# USB_MINER_CH340_c.net
KiCad netlist of a schematic drawn in EAGLE
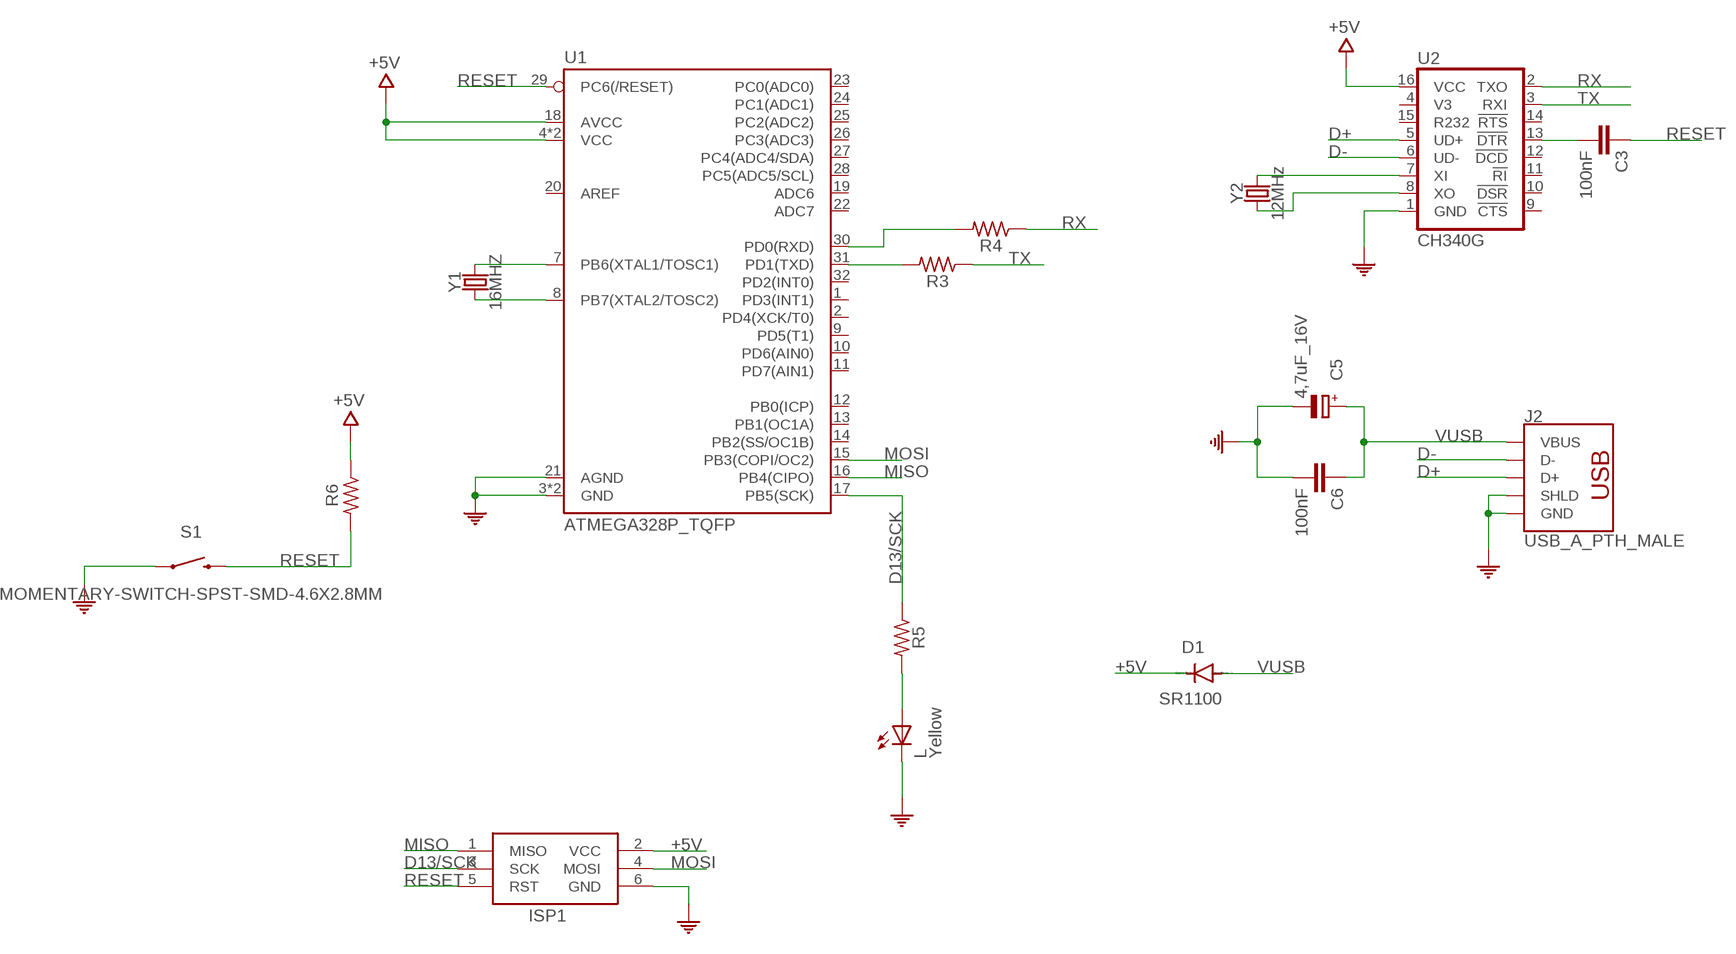
[diagram p0: schematic, sheet 1]

(export (version "E")
  (design (tool "Eeschema 10.0.6"))
  (components
    (comp (ref "C3")
      (value "100nF")
      (footprint "eagle-import:C0805K")
      (libsource (lib "eagle-import") (part "C-EUC0805K"))
    )
    (comp (ref "C5")
      (value "4,7uF_16V")
      (footprint "eagle-import:TAN-A")
      (fields (field (name "PART_NUMBER") "TAJA475MO16RNJ"))
      (libsource (lib "eagle-import") (part "0833_TAJA475MO16RNJ"))
    )
    (comp (ref "C6")
      (value "100nF")
      (footprint "eagle-import:C0805K")
      (libsource (lib "eagle-import") (part "C-EUC0805K"))
    )
    (comp (ref "D1")
      (value "SR1100")
      (footprint "eagle-import:DO-214AC")
      (libsource (lib "eagle-import") (part "DIODE-DO-214AC"))
    )
    (comp (ref "ISP1")
      (value "AVRISP-6")
      (footprint "eagle-import:AVRISP")
      (libsource (lib "eagle-import") (part "AVRISP-6"))
    )
    (comp (ref "J2")
      (value "USB_A_PTH_MALE")
      (footprint "eagle-import:USB-A-H")
      (libsource (lib "eagle-import") (part "USB_A_PTH_MALE"))
    )
    (comp (ref "L")
      (value "Yellow")
      (footprint "eagle-import:CHIPLED_0805")
      (fields (field (name "PART_NUMBER") "KPT-2012YC"))
      (libsource (lib "eagle-import") (part "0044_KPT-2012YC"))
    )
    (comp (ref "R3")
      (value "1k")
      (footprint "eagle-import:R0805")
      (libsource (lib "eagle-import") (part "R-US_R0805"))
    )
    (comp (ref "R4")
      (value "1k")
      (footprint "eagle-import:R0805")
      (libsource (lib "eagle-import") (part "R-US_R0805"))
    )
    (comp (ref "R5")
      (value "1k")
      (footprint "eagle-import:R0805")
      (libsource (lib "eagle-import") (part "R-US_R0805"))
    )
    (comp (ref "R6")
      (value "1k")
      (footprint "eagle-import:R0805")
      (libsource (lib "eagle-import") (part "R-US_R0805"))
    )
    (comp (ref "S1")
      (value "MOMENTARY-SWITCH-SPST-SMD-4.6X2.8MM")
      (footprint "eagle-import:TACTILE_SWITCH_SMD_4.6X2.8MM")
      (libsource (lib "eagle-import") (part "MOMENTARY-SWITCH-SPST-SMD-4.6X2.8MM"))
    )
    (comp (ref "U1")
      (value "ATMEGA328P_TQFP")
      (footprint "eagle-import:TQFP32-08")
      (libsource (lib "eagle-import") (part "ATMEGA328P_TQFP"))
    )
    (comp (ref "U2")
      (value "CH340G")
      (footprint "eagle-import:SO016")
      (libsource (lib "eagle-import") (part "CH340GSMD"))
    )
    (comp (ref "Y1")
      (value "16MHZ")
      (footprint "eagle-import:HC49UP")
      (libsource (lib "eagle-import") (part "CRYSTALSMD-HC49UP"))
    )
    (comp (ref "Y2")
      (value "12MHz")
      (footprint "eagle-import:HC49UP")
      (libsource (lib "eagle-import") (part "CRYSTALSMD-HC49UP"))
    )
  )
  (nets
    (net (code "1") (name "+5V") (class "Default")
      (node (ref "D1") (pin "C") (pinfunction "C_C") (pintype "passive"))
      (node (ref "ISP1") (pin "2") (pinfunction "VCC_2") (pintype "power_in"))
      (node (ref "R6") (pin "1") (pinfunction "1_1") (pintype "passive"))
      (node (ref "U1") (pin "18") (pinfunction "AVCC_18") (pintype "bidirectional"))
      (node (ref "U1") (pin "4") (pinfunction "VCC_4") (pintype "bidirectional"))
      (node (ref "U1") (pin "6") (pinfunction "VCC_6") (pintype "bidirectional"))
      (node (ref "U2") (pin "16") (pinfunction "VCC_16") (pintype "bidirectional"))
    )
    (net (code "2") (name "/D+") (class "Default")
      (node (ref "J2") (pin "D+") (pinfunction "D+_D+") (pintype "bidirectional"))
      (node (ref "U2") (pin "5") (pinfunction "UD+_5") (pintype "bidirectional"))
    )
    (net (code "3") (name "/D-") (class "Default")
      (node (ref "J2") (pin "D-") (pinfunction "D-_D-") (pintype "bidirectional"))
      (node (ref "U2") (pin "6") (pinfunction "UD-_6") (pintype "bidirectional"))
    )
    (net (code "4") (name "/D13{slash}SCK") (class "Default")
      (node (ref "ISP1") (pin "3") (pinfunction "SCK_3") (pintype "output"))
      (node (ref "R5") (pin "1") (pinfunction "1_1") (pintype "passive"))
      (node (ref "U1") (pin "17") (pinfunction "PB5(SCK)_17") (pintype "bidirectional"))
    )
    (net (code "5") (name "/MISO") (class "Default")
      (node (ref "ISP1") (pin "1") (pinfunction "MISO_1") (pintype "input"))
      (node (ref "U1") (pin "16") (pinfunction "PB4(CIPO)_16") (pintype "bidirectional"))
    )
    (net (code "6") (name "/MOSI") (class "Default")
      (node (ref "ISP1") (pin "4") (pinfunction "MOSI_4") (pintype "output"))
      (node (ref "U1") (pin "15") (pinfunction "PB3(COPI/OC2)_15") (pintype "bidirectional"))
    )
    (net (code "7") (name "/RESET") (class "Default")
      (node (ref "C3") (pin "1") (pinfunction "1_1") (pintype "passive"))
      (node (ref "ISP1") (pin "5") (pinfunction "RST_5") (pintype "output"))
      (node (ref "R6") (pin "2") (pinfunction "2_2") (pintype "passive"))
      (node (ref "S1") (pin "3") (pinfunction "2_3") (pintype "passive"))
      (node (ref "S1") (pin "4") (pinfunction "2_4") (pintype "passive"))
      (node (ref "U1") (pin "29") (pinfunction "PC6(/RESET)_29") (pintype "bidirectional"))
    )
    (net (code "8") (name "/RX") (class "Default")
      (node (ref "R4") (pin "1") (pinfunction "1_1") (pintype "passive"))
      (node (ref "U2") (pin "2") (pinfunction "TXO_2") (pintype "bidirectional"))
    )
    (net (code "9") (name "/TX") (class "Default")
      (node (ref "R3") (pin "1") (pinfunction "1_1") (pintype "passive"))
      (node (ref "U2") (pin "3") (pinfunction "RXI_3") (pintype "bidirectional"))
    )
    (net (code "10") (name "/VUSB") (class "Default")
      (node (ref "C5") (pin "1") (pinfunction "+_1") (pintype "passive"))
      (node (ref "C6") (pin "1") (pinfunction "1_1") (pintype "passive"))
      (node (ref "D1") (pin "A") (pinfunction "A_A") (pintype "passive"))
      (node (ref "J2") (pin "VBUS") (pinfunction "VBUS_VBUS") (pintype "power_in"))
    )
    (net (code "11") (name "COM") (class "Default")
      (node (ref "C5") (pin "2") (pinfunction "-_2") (pintype "passive"))
      (node (ref "C6") (pin "2") (pinfunction "2_2") (pintype "passive"))
      (node (ref "ISP1") (pin "6") (pinfunction "GND_6") (pintype "power_in"))
      (node (ref "J2") (pin "GND") (pinfunction "GND_GND") (pintype "power_in"))
      (node (ref "J2") (pin "SHLD1") (pinfunction "SHLD_SHLD1") (pintype "bidirectional"))
      (node (ref "J2") (pin "SHLD2") (pinfunction "SHLD_SHLD2") (pintype "bidirectional"))
      (node (ref "L") (pin "C") (pinfunction "C_C") (pintype "passive"))
      (node (ref "S1") (pin "1") (pinfunction "1_1") (pintype "passive"))
      (node (ref "S1") (pin "2") (pinfunction "1_2") (pintype "passive"))
      (node (ref "U1") (pin "21") (pinfunction "AGND_21") (pintype "bidirectional"))
      (node (ref "U1") (pin "3") (pinfunction "GND_3") (pintype "bidirectional"))
      (node (ref "U1") (pin "5") (pinfunction "GND_5") (pintype "bidirectional"))
      (node (ref "U2") (pin "1") (pinfunction "GND_1") (pintype "bidirectional"))
    )
    (net (code "12") (name "Net-(L-PadA)") (class "Default")
      (node (ref "L") (pin "A") (pinfunction "A_A") (pintype "passive"))
      (node (ref "R5") (pin "2") (pinfunction "2_2") (pintype "passive"))
    )
    (net (code "13") (name "Net-(U1-PB6(XTAL1{slash}TOSC1))") (class "Default")
      (node (ref "U1") (pin "7") (pinfunction "PB6(XTAL1/TOSC1)_7") (pintype "bidirectional"))
      (node (ref "Y1") (pin "2") (pinfunction "2_2") (pintype "passive"))
    )
    (net (code "14") (name "Net-(U1-PB7(XTAL2{slash}TOSC2))") (class "Default")
      (node (ref "U1") (pin "8") (pinfunction "PB7(XTAL2/TOSC2)_8") (pintype "bidirectional"))
      (node (ref "Y1") (pin "1") (pinfunction "1_1") (pintype "passive"))
    )
    (net (code "15") (name "Net-(U1-PD0(RXD))") (class "Default")
      (node (ref "R4") (pin "2") (pinfunction "2_2") (pintype "passive"))
      (node (ref "U1") (pin "30") (pinfunction "PD0(RXD)_30") (pintype "bidirectional"))
    )
    (net (code "16") (name "Net-(U1-PD1(TXD))") (class "Default")
      (node (ref "R3") (pin "2") (pinfunction "2_2") (pintype "passive"))
      (node (ref "U1") (pin "31") (pinfunction "PD1(TXD)_31") (pintype "bidirectional"))
    )
    (net (code "17") (name "Net-(U2-XI)") (class "Default")
      (node (ref "U2") (pin "7") (pinfunction "XI_7") (pintype "bidirectional"))
      (node (ref "Y2") (pin "2") (pinfunction "2_2") (pintype "passive"))
    )
    (net (code "18") (name "Net-(U2-XO)") (class "Default")
      (node (ref "U2") (pin "8") (pinfunction "XO_8") (pintype "bidirectional"))
      (node (ref "Y2") (pin "1") (pinfunction "1_1") (pintype "passive"))
    )
    (net (code "19") (name "Net-(U2-~{DTR})") (class "Default")
      (node (ref "C3") (pin "2") (pinfunction "2_2") (pintype "passive"))
      (node (ref "U2") (pin "13") (pinfunction "~{DTR}_13") (pintype "bidirectional"))
    )
    (net (code "20") (name "unconnected-(U1-ADC6-Pad19)") (class "Default")
      (node (ref "U1") (pin "19") (pinfunction "ADC6_19") (pintype "bidirectional"))
    )
    (net (code "21") (name "unconnected-(U1-ADC7-Pad22)") (class "Default")
      (node (ref "U1") (pin "22") (pinfunction "ADC7_22") (pintype "bidirectional"))
    )
    (net (code "22") (name "unconnected-(U1-AREF-Pad20)") (class "Default")
      (node (ref "U1") (pin "20") (pinfunction "AREF_20") (pintype "bidirectional"))
    )
    (net (code "23") (name "unconnected-(U1-PB0(ICP)-Pad12)") (class "Default")
      (node (ref "U1") (pin "12") (pinfunction "PB0(ICP)_12") (pintype "bidirectional"))
    )
    (net (code "24") (name "unconnected-(U1-PB1(OC1A)-Pad13)") (class "Default")
      (node (ref "U1") (pin "13") (pinfunction "PB1(OC1A)_13") (pintype "bidirectional"))
    )
    (net (code "25") (name "unconnected-(U1-PB2(SS{slash}OC1B)-Pad14)") (class "Default")
      (node (ref "U1") (pin "14") (pinfunction "PB2(SS/OC1B)_14") (pintype "bidirectional"))
    )
    (net (code "26") (name "unconnected-(U1-PC0(ADC0)-Pad23)") (class "Default")
      (node (ref "U1") (pin "23") (pinfunction "PC0(ADC0)_23") (pintype "bidirectional"))
    )
    (net (code "27") (name "unconnected-(U1-PC1(ADC1)-Pad24)") (class "Default")
      (node (ref "U1") (pin "24") (pinfunction "PC1(ADC1)_24") (pintype "bidirectional"))
    )
    (net (code "28") (name "unconnected-(U1-PC2(ADC2)-Pad25)") (class "Default")
      (node (ref "U1") (pin "25") (pinfunction "PC2(ADC2)_25") (pintype "bidirectional"))
    )
    (net (code "29") (name "unconnected-(U1-PC3(ADC3)-Pad26)") (class "Default")
      (node (ref "U1") (pin "26") (pinfunction "PC3(ADC3)_26") (pintype "bidirectional"))
    )
    (net (code "30") (name "unconnected-(U1-PC4(ADC4{slash}SDA)-Pad27)") (class "Default")
      (node (ref "U1") (pin "27") (pinfunction "PC4(ADC4/SDA)_27") (pintype "bidirectional"))
    )
    (net (code "31") (name "unconnected-(U1-PC5(ADC5{slash}SCL)-Pad28)") (class "Default")
      (node (ref "U1") (pin "28") (pinfunction "PC5(ADC5/SCL)_28") (pintype "bidirectional"))
    )
    (net (code "32") (name "unconnected-(U1-PD2(INT0)-Pad32)") (class "Default")
      (node (ref "U1") (pin "32") (pinfunction "PD2(INT0)_32") (pintype "bidirectional"))
    )
    (net (code "33") (name "unconnected-(U1-PD3(INT1)-Pad1)") (class "Default")
      (node (ref "U1") (pin "1") (pinfunction "PD3(INT1)_1") (pintype "bidirectional"))
    )
    (net (code "34") (name "unconnected-(U1-PD4(XCK{slash}T0)-Pad2)") (class "Default")
      (node (ref "U1") (pin "2") (pinfunction "PD4(XCK/T0)_2") (pintype "bidirectional"))
    )
    (net (code "35") (name "unconnected-(U1-PD5(T1)-Pad9)") (class "Default")
      (node (ref "U1") (pin "9") (pinfunction "PD5(T1)_9") (pintype "bidirectional"))
    )
    (net (code "36") (name "unconnected-(U1-PD6(AIN0)-Pad10)") (class "Default")
      (node (ref "U1") (pin "10") (pinfunction "PD6(AIN0)_10") (pintype "bidirectional"))
    )
    (net (code "37") (name "unconnected-(U1-PD7(AIN1)-Pad11)") (class "Default")
      (node (ref "U1") (pin "11") (pinfunction "PD7(AIN1)_11") (pintype "bidirectional"))
    )
    (net (code "38") (name "unconnected-(U2-R232-Pad15)") (class "Default")
      (node (ref "U2") (pin "15") (pinfunction "R232_15") (pintype "bidirectional"))
    )
    (net (code "39") (name "unconnected-(U2-V3-Pad4)") (class "Default")
      (node (ref "U2") (pin "4") (pinfunction "V3_4") (pintype "bidirectional"))
    )
    (net (code "40") (name "unconnected-(U2-~{CTS}-Pad9)") (class "Default")
      (node (ref "U2") (pin "9") (pinfunction "~{CTS}_9") (pintype "bidirectional"))
    )
    (net (code "41") (name "unconnected-(U2-~{DCD}-Pad12)") (class "Default")
      (node (ref "U2") (pin "12") (pinfunction "~{DCD}_12") (pintype "bidirectional"))
    )
    (net (code "42") (name "unconnected-(U2-~{DSR}-Pad10)") (class "Default")
      (node (ref "U2") (pin "10") (pinfunction "~{DSR}_10") (pintype "bidirectional"))
    )
    (net (code "43") (name "unconnected-(U2-~{RI}-Pad11)") (class "Default")
      (node (ref "U2") (pin "11") (pinfunction "~{RI}_11") (pintype "bidirectional"))
    )
    (net (code "44") (name "unconnected-(U2-~{RTS}-Pad14)") (class "Default")
      (node (ref "U2") (pin "14") (pinfunction "~{RTS}_14") (pintype "bidirectional"))
    )
  )
)
